# attiny-quickstart.net
KiCad netlist of a schematic drawn in EAGLE
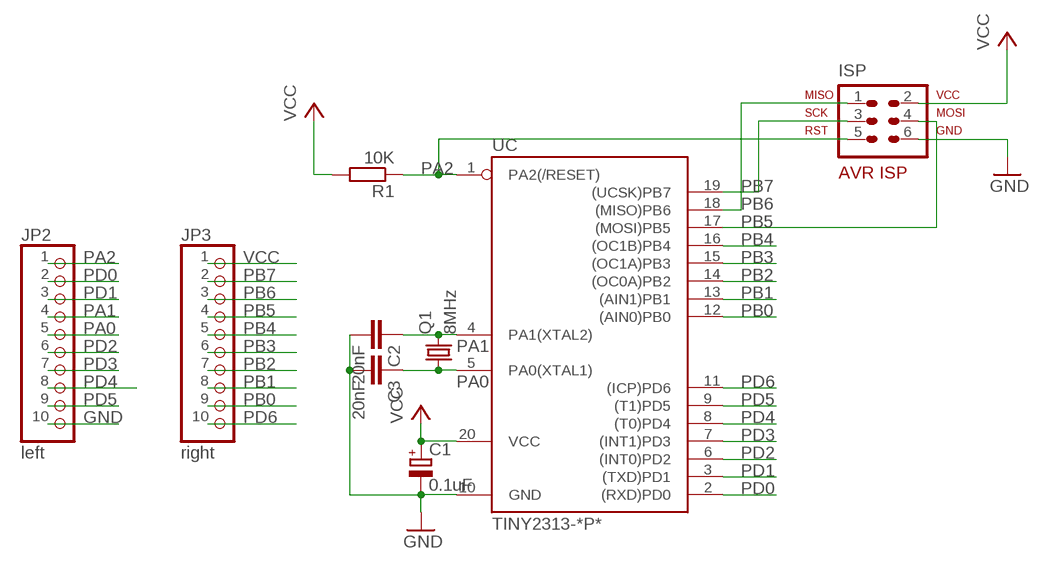
[diagram p0: schematic, sheet 1]

(export (version "E")
  (design (tool "Eeschema 10.0.6"))
  (components
    (comp (ref "C1")
      (value "0.1uF")
      (footprint "eagle-import:E2,5-6E")
      (libsource (lib "eagle-import") (part "CPOL-EUE2,5-6E"))
    )
    (comp (ref "C2")
      (value "20nF")
      (footprint "eagle-import:C025-024X044")
      (libsource (lib "eagle-import") (part "C-EU025-024X044"))
    )
    (comp (ref "C3")
      (value "20nF")
      (footprint "eagle-import:C025-024X044")
      (libsource (lib "eagle-import") (part "C-EU025-024X044"))
    )
    (comp (ref "ISP")
      (value "AVR-ISP-6VERT")
      (footprint "eagle-import:AVR-ISP-6")
      (libsource (lib "eagle-import") (part "AVR-ISP-6VERT"))
    )
    (comp (ref "JP2")
      (value "left")
      (footprint "eagle-import:1X10")
      (libsource (lib "eagle-import") (part "PINHD-1X10"))
    )
    (comp (ref "JP3")
      (value "right")
      (footprint "eagle-import:1X10")
      (libsource (lib "eagle-import") (part "PINHD-1X10"))
    )
    (comp (ref "Q1")
      (value "8MHz")
      (footprint "eagle-import:HC49_S")
      (libsource (lib "eagle-import") (part "CRYSTALHC49S"))
    )
    (comp (ref "R1")
      (value "10K")
      (footprint "eagle-import:0204_5")
      (libsource (lib "eagle-import") (part "R-EU_0204/5"))
    )
    (comp (ref "UC")
      (value "TINY2313-*P*")
      (footprint "eagle-import:DIL20")
      (libsource (lib "eagle-import") (part "TINY2313-P"))
    )
  )
  (nets
    (net (code "1") (name "/PA0") (class "Default")
      (node (ref "C3") (pin "1") (pinfunction "1_1") (pintype "passive"))
      (node (ref "JP2") (pin "5") (pinfunction "5_5") (pintype "passive"))
      (node (ref "Q1") (pin "1") (pinfunction "1_1") (pintype "passive"))
      (node (ref "UC") (pin "5") (pinfunction "PA0(XTAL1)_5") (pintype "bidirectional"))
    )
    (net (code "2") (name "/PA1") (class "Default")
      (node (ref "C2") (pin "1") (pinfunction "1_1") (pintype "passive"))
      (node (ref "JP2") (pin "4") (pinfunction "4_4") (pintype "passive"))
      (node (ref "Q1") (pin "2") (pinfunction "2_2") (pintype "passive"))
      (node (ref "UC") (pin "4") (pinfunction "PA1(XTAL2)_4") (pintype "bidirectional"))
    )
    (net (code "3") (name "/PA2") (class "Default")
      (node (ref "ISP") (pin "5") (pinfunction "5_5") (pintype "passive"))
      (node (ref "JP2") (pin "1") (pinfunction "1_1") (pintype "passive"))
      (node (ref "R1") (pin "1") (pinfunction "1_1") (pintype "passive"))
      (node (ref "UC") (pin "1") (pinfunction "PA2(/RESET)_1") (pintype "input"))
    )
    (net (code "4") (name "/PB0") (class "Default")
      (node (ref "JP3") (pin "9") (pinfunction "9_9") (pintype "passive"))
      (node (ref "UC") (pin "12") (pinfunction "(AIN0)PB0_12") (pintype "bidirectional"))
    )
    (net (code "5") (name "/PB1") (class "Default")
      (node (ref "JP3") (pin "8") (pinfunction "8_8") (pintype "passive"))
      (node (ref "UC") (pin "13") (pinfunction "(AIN1)PB1_13") (pintype "bidirectional"))
    )
    (net (code "6") (name "/PB2") (class "Default")
      (node (ref "JP3") (pin "7") (pinfunction "7_7") (pintype "passive"))
      (node (ref "UC") (pin "14") (pinfunction "(OC0A)PB2_14") (pintype "bidirectional"))
    )
    (net (code "7") (name "/PB3") (class "Default")
      (node (ref "JP3") (pin "6") (pinfunction "6_6") (pintype "passive"))
      (node (ref "UC") (pin "15") (pinfunction "(OC1A)PB3_15") (pintype "bidirectional"))
    )
    (net (code "8") (name "/PB4") (class "Default")
      (node (ref "JP3") (pin "5") (pinfunction "5_5") (pintype "passive"))
      (node (ref "UC") (pin "16") (pinfunction "(OC1B)PB4_16") (pintype "bidirectional"))
    )
    (net (code "9") (name "/PB5") (class "Default")
      (node (ref "ISP") (pin "4") (pinfunction "4_4") (pintype "passive"))
      (node (ref "JP3") (pin "4") (pinfunction "4_4") (pintype "passive"))
      (node (ref "UC") (pin "17") (pinfunction "(MOSI)PB5_17") (pintype "bidirectional"))
    )
    (net (code "10") (name "/PB6") (class "Default")
      (node (ref "ISP") (pin "1") (pinfunction "1_1") (pintype "passive"))
      (node (ref "JP3") (pin "3") (pinfunction "3_3") (pintype "passive"))
      (node (ref "UC") (pin "18") (pinfunction "(MISO)PB6_18") (pintype "bidirectional"))
    )
    (net (code "11") (name "/PB7") (class "Default")
      (node (ref "ISP") (pin "3") (pinfunction "3_3") (pintype "passive"))
      (node (ref "JP3") (pin "2") (pinfunction "2_2") (pintype "passive"))
      (node (ref "UC") (pin "19") (pinfunction "(UCSK)PB7_19") (pintype "bidirectional"))
    )
    (net (code "12") (name "/PD0") (class "Default")
      (node (ref "JP2") (pin "2") (pinfunction "2_2") (pintype "passive"))
      (node (ref "UC") (pin "2") (pinfunction "(RXD)PD0_2") (pintype "bidirectional"))
    )
    (net (code "13") (name "/PD1") (class "Default")
      (node (ref "JP2") (pin "3") (pinfunction "3_3") (pintype "passive"))
      (node (ref "UC") (pin "3") (pinfunction "(TXD)PD1_3") (pintype "bidirectional"))
    )
    (net (code "14") (name "/PD2") (class "Default")
      (node (ref "JP2") (pin "6") (pinfunction "6_6") (pintype "passive"))
      (node (ref "UC") (pin "6") (pinfunction "(INT0)PD2_6") (pintype "bidirectional"))
    )
    (net (code "15") (name "/PD3") (class "Default")
      (node (ref "JP2") (pin "7") (pinfunction "7_7") (pintype "passive"))
      (node (ref "UC") (pin "7") (pinfunction "(INT1)PD3_7") (pintype "bidirectional"))
    )
    (net (code "16") (name "/PD4") (class "Default")
      (node (ref "JP2") (pin "8") (pinfunction "8_8") (pintype "passive"))
      (node (ref "UC") (pin "8") (pinfunction "(T0)PD4_8") (pintype "bidirectional"))
    )
    (net (code "17") (name "/PD5") (class "Default")
      (node (ref "JP2") (pin "9") (pinfunction "9_9") (pintype "passive"))
      (node (ref "UC") (pin "9") (pinfunction "(T1)PD5_9") (pintype "bidirectional"))
    )
    (net (code "18") (name "/PD6") (class "Default")
      (node (ref "JP3") (pin "10") (pinfunction "10_10") (pintype "passive"))
      (node (ref "UC") (pin "11") (pinfunction "(ICP)PD6_11") (pintype "bidirectional"))
    )
    (net (code "19") (name "GND") (class "Default")
      (node (ref "C1") (pin "-") (pinfunction "-_-") (pintype "passive"))
      (node (ref "C2") (pin "2") (pinfunction "2_2") (pintype "passive"))
      (node (ref "C3") (pin "2") (pinfunction "2_2") (pintype "passive"))
      (node (ref "ISP") (pin "6") (pinfunction "6_6") (pintype "passive"))
      (node (ref "JP2") (pin "10") (pinfunction "10_10") (pintype "passive"))
      (node (ref "UC") (pin "10") (pinfunction "GND_10") (pintype "power_in"))
    )
    (net (code "20") (name "VCC") (class "Default")
      (node (ref "C1") (pin "+") (pinfunction "+_+") (pintype "passive"))
      (node (ref "ISP") (pin "2") (pinfunction "2_2") (pintype "passive"))
      (node (ref "JP3") (pin "1") (pinfunction "1_1") (pintype "passive"))
      (node (ref "R1") (pin "2") (pinfunction "2_2") (pintype "passive"))
      (node (ref "UC") (pin "20") (pinfunction "VCC_20") (pintype "power_in"))
    )
  )
)
